# Mobile_adapter_5V_1A_LQ.net
KiCad netlist of a schematic drawn in Altium Designer
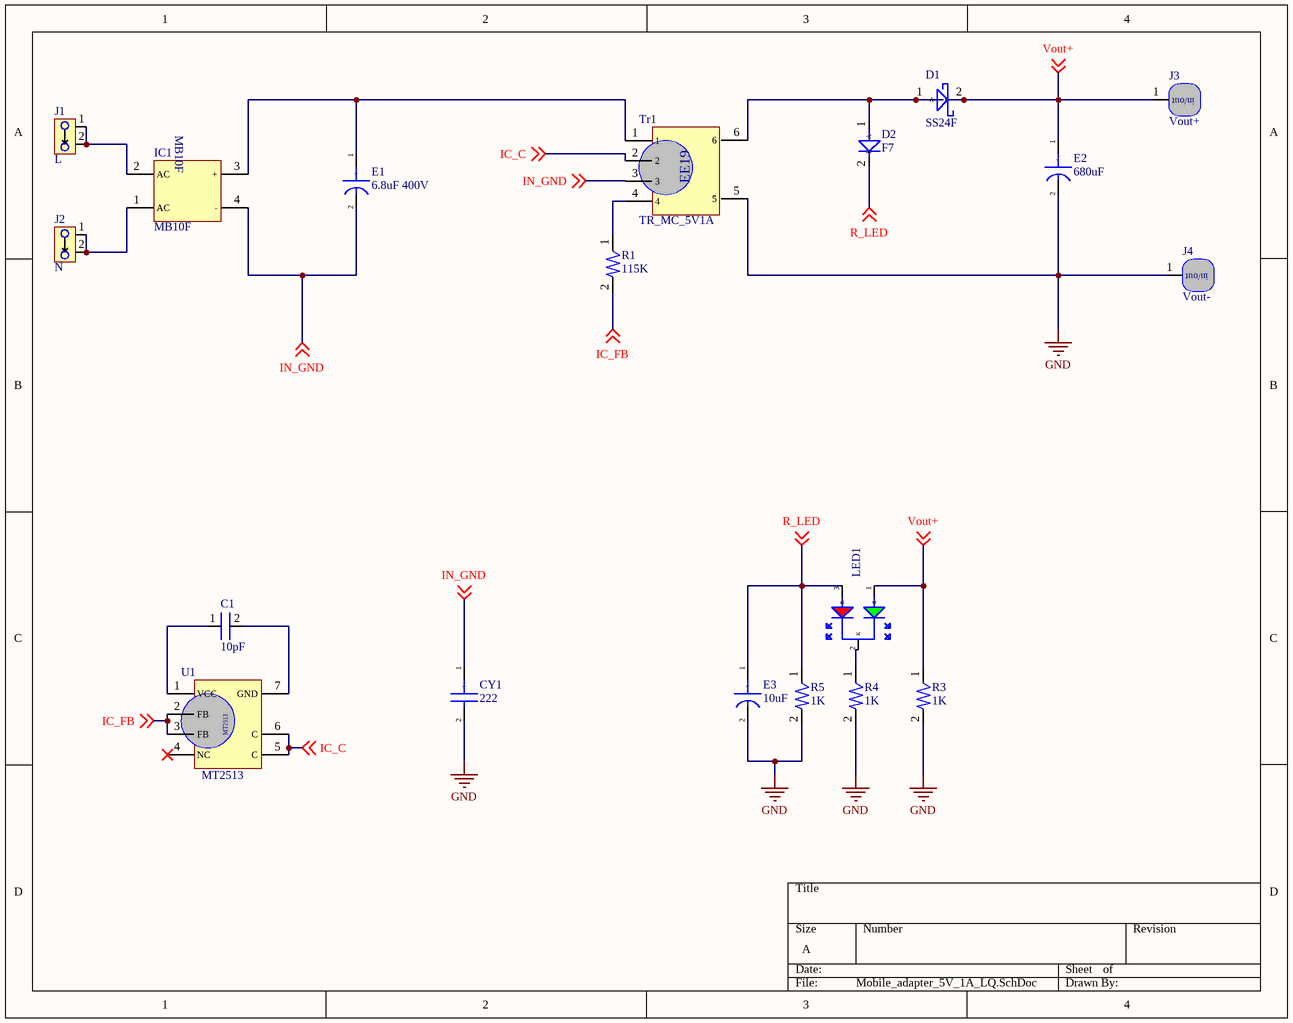
[diagram p0: Mobile_adapter_5V_1A_LQ.SchDoc]

(export (version "E")
  (design (tool "Eeschema 10.0.6"))
  (components
    (comp (ref "C1")
      (value "10pF")
      (footprint "C_0603")
      (description "25V 10pF C0G ±5% 0603 Multilayer Ceramic Capacitors MLCC - SMD/SMT ROHS")
      (libsource (lib "Custom pcb schamatic") (part "C_0603"))
    )
    (comp (ref "CY1")
      (value "222")
      (footprint "C_TH_104/102")
      (description "Keltron 222 1kv Capacitor")
      (libsource (lib "Custom pcb schamatic") (part "C_TH_104/102"))
    )
    (comp (ref "D1")
      (value "SS24F")
      (footprint "SMAF")
      (libsource (lib "Custom pcb schamatic") (part "D_SS24F_SK_SMAF"))
    )
    (comp (ref "D2")
      (value "F7")
      (footprint "SOD123F-F7")
      (libsource (lib "Custom pcb schamatic") (part "D_F7_SOD123"))
    )
    (comp (ref "E1")
      (value "6.8uF 400V")
      (footprint "CAP_D8XL13")
      (description "6.8uF 400V ±20% Plugin,D8xL12mm Aluminum Electrolytic Capacitors - Leaded ROHS")
      (libsource (lib "Custom pcb schamatic") (part "C_D8XL13"))
    )
    (comp (ref "E2")
      (value "680uF")
      (footprint "CAP_D6.5XL12")
      (description "680uF 6.3V ±20% Plugin,D6.3xL12mm Aluminum Electrolytic Capacitors - Leaded ROHS")
      (libsource (lib "Custom pcb schamatic") (part "C_D6.5XL12"))
    )
    (comp (ref "E3")
      (value "10uF")
      (footprint "CAP_D5XL11")
      (description "10uF 50V ±20% Plugin,D5xL7mm Aluminum Electrolytic Capacitors - Leaded ROHS")
      (libsource (lib "Custom pcb schamatic") (part "C_D5XL11"))
    )
    (comp (ref "IC1")
      (value "MB10F")
      (footprint "MB10F")
      (description "30A 1.1V@800mA 800mA 1kV MBF Bridge Rectifiers ROHS")
      (libsource (lib "Custom pcb schamatic") (part "MB10F"))
    )
    (comp (ref "J1")
      (value "L")
      (footprint "MMT Metal shrapnel connector")
      (description "Metal Shrapnel mmt connector mobile charger")
      (libsource (lib "Custom pcb schamatic") (part "Metal Shrapnel mmt connector"))
    )
    (comp (ref "J2")
      (value "N")
      (footprint "MMT Metal shrapnel connector")
      (description "Metal Shrapnel mmt connector mobile charger")
      (libsource (lib "Custom pcb schamatic") (part "Metal Shrapnel mmt connector"))
    )
    (comp (ref "J3")
      (value "Vout+")
      (footprint "Wire solder connector _SMD - duplicate")
      (libsource (lib "Custom pcb schamatic") (part "Wire solder connector _SMD"))
    )
    (comp (ref "J4")
      (value "Vout-")
      (footprint "Wire solder connector _SMD - duplicate")
      (libsource (lib "Custom pcb schamatic") (part "Wire solder connector _SMD"))
    )
    (comp (ref "LED1")
      (value "LED 3mm RG Com cathod")
      (footprint "LED_RG_3mm")
      (description "Red Green Common Cathode  P=2.54mm")
      (libsource (lib "Custom pcb schamatic") (part "LED 3mm RG Com cathod"))
    )
    (comp (ref "R1")
      (value "115K")
      (footprint "R_0603")
      (description "100mW Thin Film Resistor ±50ppm/℃ ±0.1% 115kΩ 0603 Chip Resistor - Surface Mount ROHS")
      (libsource (lib "Custom pcb schamatic") (part "R_0603"))
    )
    (comp (ref "R3")
      (value "1K")
      (footprint "R_0603")
      (description "100mW Thick Film Resistors 75V ±100ppm/℃ ±1% 1kΩ 0603 Chip Resistor - Surface Mount ROHS")
      (libsource (lib "Custom pcb schamatic") (part "R_0603"))
    )
    (comp (ref "R4")
      (value "1K")
      (footprint "R_0603")
      (description "100mW Thick Film Resistors 75V ±100ppm/℃ ±1% 1kΩ 0603 Chip Resistor - Surface Mount ROHS")
      (libsource (lib "Custom pcb schamatic") (part "R_0603"))
    )
    (comp (ref "R5")
      (value "1K")
      (footprint "R_0603")
      (description "100mW Thick Film Resistors 75V ±100ppm/℃ ±1% 1kΩ 0603 Chip Resistor - Surface Mount ROHS")
      (libsource (lib "Custom pcb schamatic") (part "R_0603"))
    )
    (comp (ref "Tr1")
      (value "TR_MC_5V1A")
      (footprint "T_EE19_5V1A")
      (libsource (lib "Custom pcb schamatic") (part "T_EE19_5V1A"))
    )
    (comp (ref "U1")
      (value "MT2513")
      (footprint "SOP8-7")
      (description "MT2513 SOP8 Integrated Circuits")
      (libsource (lib "Custom pcb schamatic") (part "MT2513"))
    )
  )
  (nets
    (net (code "1") (name "GND") (class "Default")
      (node (ref "CY1") (pin "2") (pinfunction "-_2") (pintype "passive"))
      (node (ref "E2") (pin "2") (pinfunction "-_2") (pintype "passive"))
      (node (ref "E3") (pin "2") (pinfunction "-_2") (pintype "passive"))
      (node (ref "J4") (pin "1") (pinfunction "1_1") (pintype "passive"))
      (node (ref "R3") (pin "2") (pinfunction "2_2") (pintype "passive"))
      (node (ref "R4") (pin "2") (pinfunction "2_2") (pintype "passive"))
      (node (ref "R5") (pin "2") (pinfunction "2_2") (pintype "passive"))
      (node (ref "Tr1") (pin "5") (pinfunction "5_5") (pintype "passive"))
    )
    (net (code "2") (name "IC_C") (class "Default")
      (node (ref "Tr1") (pin "2") (pinfunction "2_2") (pintype "passive"))
      (node (ref "U1") (pin "5") (pinfunction "C_5") (pintype "passive"))
      (node (ref "U1") (pin "6") (pinfunction "C_6") (pintype "passive"))
    )
    (net (code "3") (name "IC_FB") (class "Default")
      (node (ref "R1") (pin "2") (pinfunction "2_2") (pintype "passive"))
      (node (ref "U1") (pin "2") (pinfunction "FB_2") (pintype "passive"))
      (node (ref "U1") (pin "3") (pinfunction "FB_3") (pintype "passive"))
    )
    (net (code "4") (name "IN_GND") (class "Default")
      (node (ref "CY1") (pin "1") (pinfunction "+_1") (pintype "passive"))
      (node (ref "E1") (pin "2") (pinfunction "-_2") (pintype "passive"))
      (node (ref "IC1") (pin "4") (pinfunction "-_4") (pintype "passive"))
      (node (ref "Tr1") (pin "3") (pinfunction "3_3") (pintype "passive"))
    )
    (net (code "5") (name "Net-(D1-A)") (class "Default")
      (node (ref "D1") (pin "1") (pinfunction "A_1") (pintype "passive"))
      (node (ref "D2") (pin "1") (pinfunction "A_1") (pintype "passive"))
      (node (ref "Tr1") (pin "6") (pinfunction "6_6") (pintype "passive"))
    )
    (net (code "6") (name "Net-(E1-+)") (class "Default")
      (node (ref "E1") (pin "1") (pinfunction "+_1") (pintype "passive"))
      (node (ref "IC1") (pin "3") (pinfunction "+_3") (pintype "passive"))
      (node (ref "Tr1") (pin "1") (pinfunction "1_1") (pintype "passive"))
    )
    (net (code "7") (name "Net-(IC1-AC-Pad1)") (class "Default")
      (node (ref "IC1") (pin "1") (pinfunction "AC_1") (pintype "passive"))
      (node (ref "J2") (pin "1") (pinfunction "1_1") (pintype "passive"))
      (node (ref "J2") (pin "2") (pinfunction "2_2") (pintype "passive"))
    )
    (net (code "8") (name "Net-(IC1-AC-Pad2)") (class "Default")
      (node (ref "IC1") (pin "2") (pinfunction "AC_2") (pintype "passive"))
      (node (ref "J1") (pin "1") (pinfunction "1_1") (pintype "passive"))
      (node (ref "J1") (pin "2") (pinfunction "2_2") (pintype "passive"))
    )
    (net (code "9") (name "Net-(LED1-K)") (class "Default")
      (node (ref "LED1") (pin "2") (pinfunction "K_2") (pintype "passive"))
      (node (ref "R4") (pin "1") (pinfunction "1_1") (pintype "passive"))
    )
    (net (code "10") (name "Net-(R1-Pad1)") (class "Default")
      (node (ref "R1") (pin "1") (pinfunction "1_1") (pintype "passive"))
      (node (ref "Tr1") (pin "4") (pinfunction "4_4") (pintype "passive"))
    )
    (net (code "11") (name "Net-(U1-GND)") (class "Default")
      (node (ref "C1") (pin "2") (pinfunction "2_2") (pintype "passive"))
      (node (ref "U1") (pin "7") (pinfunction "GND_7") (pintype "passive"))
    )
    (net (code "12") (name "Net-(U1-VCC)") (class "Default")
      (node (ref "C1") (pin "1") (pinfunction "1_1") (pintype "passive"))
      (node (ref "U1") (pin "1") (pinfunction "VCC_1") (pintype "passive"))
    )
    (net (code "13") (name "R_LED") (class "Default")
      (node (ref "D2") (pin "2") (pinfunction "K_2") (pintype "passive"))
      (node (ref "E3") (pin "1") (pinfunction "+_1") (pintype "passive"))
      (node (ref "LED1") (pin "3") (pinfunction "R_3") (pintype "passive"))
      (node (ref "R5") (pin "1") (pinfunction "1_1") (pintype "passive"))
    )
    (net (code "14") (name "Vout+") (class "Default")
      (node (ref "D1") (pin "2") (pinfunction "K_2") (pintype "passive"))
      (node (ref "E2") (pin "1") (pinfunction "+_1") (pintype "passive"))
      (node (ref "J3") (pin "1") (pinfunction "1_1") (pintype "passive"))
      (node (ref "LED1") (pin "1") (pinfunction "G_1") (pintype "passive"))
      (node (ref "R3") (pin "1") (pinfunction "1_1") (pintype "passive"))
    )
    (net (code "15") (name "unconnected-(U1-NC-Pad4)") (class "Default")
      (node (ref "U1") (pin "4") (pinfunction "NC_4") (pintype "passive+no_connect"))
    )
  )
)
